# HighPowerWS2801_v2_smd.net
KiCad netlist of a schematic drawn in EAGLE
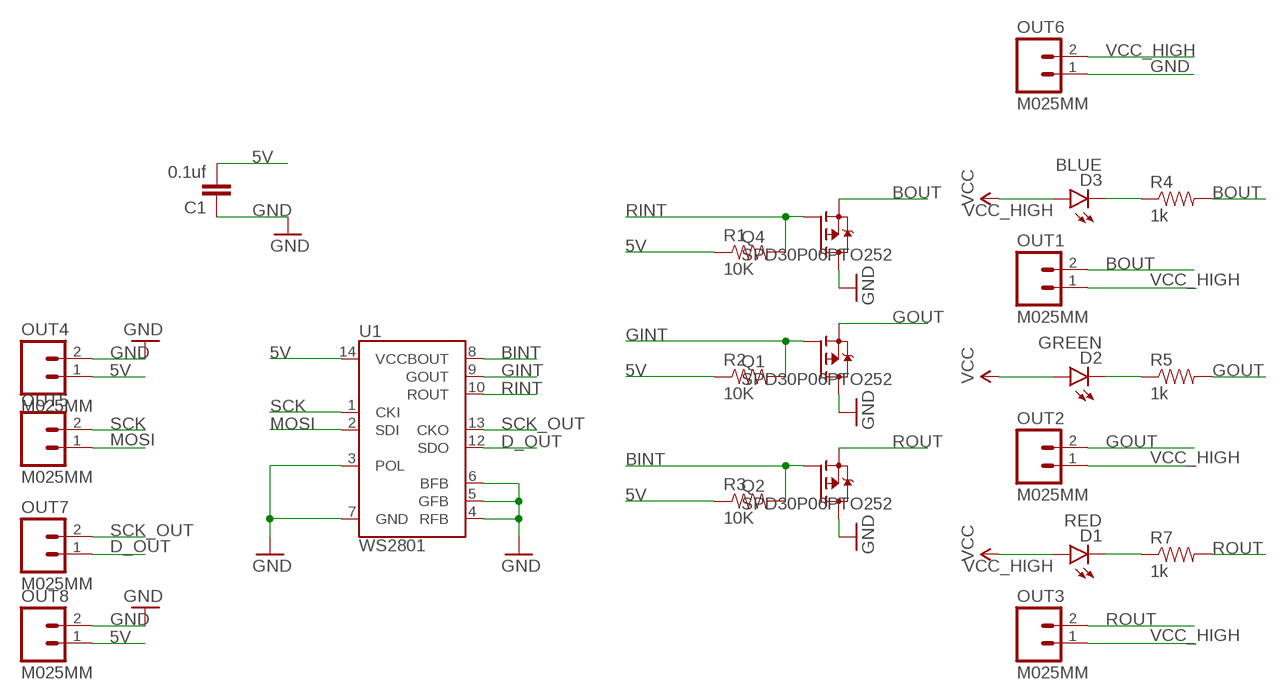
[diagram p0: schematic, sheet 1]

(export (version "E")
  (design (tool "Eeschema 10.0.6"))
  (components
    (comp (ref "C1")
      (value "0.1uf")
      (footprint "eagle-import:0603-CAP")
      (libsource (lib "eagle-import") (part "CAP0603-CAP"))
    )
    (comp (ref "D1")
      (value "RED")
      (footprint "eagle-import:LED-0603")
      (libsource (lib "eagle-import") (part "LED-RED0603"))
    )
    (comp (ref "D2")
      (value "GREEN")
      (footprint "eagle-import:LED-0603")
      (libsource (lib "eagle-import") (part "LED-GREEN0603"))
    )
    (comp (ref "D3")
      (value "BLUE")
      (footprint "eagle-import:LED-0603")
      (libsource (lib "eagle-import") (part "LED-BLUE0603"))
    )
    (comp (ref "OUT1")
      (value "M025MM")
      (footprint "eagle-import:SCREWTERMINAL-5MM-2")
      (libsource (lib "eagle-import") (part "M025MM"))
    )
    (comp (ref "OUT2")
      (value "M025MM")
      (footprint "eagle-import:SCREWTERMINAL-5MM-2")
      (libsource (lib "eagle-import") (part "M025MM"))
    )
    (comp (ref "OUT3")
      (value "M025MM")
      (footprint "eagle-import:SCREWTERMINAL-5MM-2")
      (libsource (lib "eagle-import") (part "M025MM"))
    )
    (comp (ref "OUT4")
      (value "M025MM")
      (footprint "eagle-import:SCREWTERMINAL-5MM-2")
      (libsource (lib "eagle-import") (part "M025MM"))
    )
    (comp (ref "OUT5")
      (value "M025MM")
      (footprint "eagle-import:SCREWTERMINAL-5MM-2")
      (libsource (lib "eagle-import") (part "M025MM"))
    )
    (comp (ref "OUT6")
      (value "M025MM")
      (footprint "eagle-import:SCREWTERMINAL-5MM-2")
      (libsource (lib "eagle-import") (part "M025MM"))
    )
    (comp (ref "OUT7")
      (value "M025MM")
      (footprint "eagle-import:SCREWTERMINAL-5MM-2")
      (libsource (lib "eagle-import") (part "M025MM"))
    )
    (comp (ref "OUT8")
      (value "M025MM")
      (footprint "eagle-import:SCREWTERMINAL-5MM-2")
      (libsource (lib "eagle-import") (part "M025MM"))
    )
    (comp (ref "Q1")
      (value "SPD30P06PTO252")
      (footprint "eagle-import:TO252")
      (libsource (lib "eagle-import") (part "SPD30P06PTO252"))
    )
    (comp (ref "Q2")
      (value "SPD30P06PTO252")
      (footprint "eagle-import:TO252")
      (libsource (lib "eagle-import") (part "SPD30P06PTO252"))
    )
    (comp (ref "Q4")
      (value "SPD30P06PTO252")
      (footprint "eagle-import:TO252")
      (libsource (lib "eagle-import") (part "SPD30P06PTO252"))
    )
    (comp (ref "R1")
      (value "10K")
      (footprint "eagle-import:0603-RES")
      (libsource (lib "eagle-import") (part "RESISTOR0603"))
    )
    (comp (ref "R2")
      (value "10K")
      (footprint "eagle-import:0603-RES")
      (libsource (lib "eagle-import") (part "RESISTOR0603"))
    )
    (comp (ref "R3")
      (value "10K")
      (footprint "eagle-import:0603-RES")
      (libsource (lib "eagle-import") (part "RESISTOR0603"))
    )
    (comp (ref "R4")
      (value "1k")
      (footprint "eagle-import:0603-RES")
      (libsource (lib "eagle-import") (part "RESISTOR0603"))
    )
    (comp (ref "R5")
      (value "1k")
      (footprint "eagle-import:0603-RES")
      (libsource (lib "eagle-import") (part "RESISTOR0603"))
    )
    (comp (ref "R7")
      (value "1k")
      (footprint "eagle-import:0603-RES")
      (libsource (lib "eagle-import") (part "RESISTOR0603"))
    )
    (comp (ref "U1")
      (value "WS2801")
      (footprint "eagle-import:SOP-14")
      (libsource (lib "eagle-import") (part "WS2801"))
    )
  )
  (nets
    (net (code "1") (name "/5V") (class "Default")
      (node (ref "C1") (pin "2") (pinfunction "2_2") (pintype "passive"))
      (node (ref "OUT4") (pin "1") (pinfunction "1_1") (pintype "passive"))
      (node (ref "OUT8") (pin "1") (pinfunction "1_1") (pintype "passive"))
      (node (ref "R1") (pin "1") (pinfunction "1_1") (pintype "passive"))
      (node (ref "R2") (pin "1") (pinfunction "1_1") (pintype "passive"))
      (node (ref "R3") (pin "1") (pinfunction "1_1") (pintype "passive"))
      (node (ref "U1") (pin "14") (pinfunction "VCC_14") (pintype "bidirectional"))
    )
    (net (code "2") (name "/BINT") (class "Default")
      (node (ref "Q2") (pin "1") (pinfunction "G_1") (pintype "passive"))
      (node (ref "R3") (pin "2") (pinfunction "2_2") (pintype "passive"))
      (node (ref "U1") (pin "8") (pinfunction "BOUT_8") (pintype "bidirectional"))
    )
    (net (code "3") (name "/BOUT") (class "Default")
      (node (ref "OUT1") (pin "2") (pinfunction "2_2") (pintype "passive"))
      (node (ref "Q4") (pin "2") (pinfunction "S_2") (pintype "passive"))
      (node (ref "R4") (pin "2") (pinfunction "2_2") (pintype "passive"))
    )
    (net (code "4") (name "/D_OUT") (class "Default")
      (node (ref "OUT7") (pin "1") (pinfunction "1_1") (pintype "passive"))
      (node (ref "U1") (pin "12") (pinfunction "SDO_12") (pintype "bidirectional"))
    )
    (net (code "5") (name "/GINT") (class "Default")
      (node (ref "Q1") (pin "1") (pinfunction "G_1") (pintype "passive"))
      (node (ref "R2") (pin "2") (pinfunction "2_2") (pintype "passive"))
      (node (ref "U1") (pin "9") (pinfunction "GOUT_9") (pintype "bidirectional"))
    )
    (net (code "6") (name "/GOUT") (class "Default")
      (node (ref "OUT2") (pin "2") (pinfunction "2_2") (pintype "passive"))
      (node (ref "Q1") (pin "2") (pinfunction "S_2") (pintype "passive"))
      (node (ref "R5") (pin "2") (pinfunction "2_2") (pintype "passive"))
    )
    (net (code "7") (name "/MOSI") (class "Default")
      (node (ref "OUT5") (pin "1") (pinfunction "1_1") (pintype "passive"))
      (node (ref "U1") (pin "2") (pinfunction "SDI_2") (pintype "bidirectional"))
    )
    (net (code "8") (name "/RINT") (class "Default")
      (node (ref "Q4") (pin "1") (pinfunction "G_1") (pintype "passive"))
      (node (ref "R1") (pin "2") (pinfunction "2_2") (pintype "passive"))
      (node (ref "U1") (pin "10") (pinfunction "ROUT_10") (pintype "bidirectional"))
    )
    (net (code "9") (name "/ROUT") (class "Default")
      (node (ref "OUT3") (pin "2") (pinfunction "2_2") (pintype "passive"))
      (node (ref "Q2") (pin "2") (pinfunction "S_2") (pintype "passive"))
      (node (ref "R7") (pin "2") (pinfunction "2_2") (pintype "passive"))
    )
    (net (code "10") (name "/SCK") (class "Default")
      (node (ref "OUT5") (pin "2") (pinfunction "2_2") (pintype "passive"))
      (node (ref "U1") (pin "1") (pinfunction "CKI_1") (pintype "bidirectional"))
    )
    (net (code "11") (name "/SCK_OUT") (class "Default")
      (node (ref "OUT7") (pin "2") (pinfunction "2_2") (pintype "passive"))
      (node (ref "U1") (pin "13") (pinfunction "CKO_13") (pintype "bidirectional"))
    )
    (net (code "12") (name "GND") (class "Default")
      (node (ref "C1") (pin "1") (pinfunction "1_1") (pintype "passive"))
      (node (ref "OUT4") (pin "2") (pinfunction "2_2") (pintype "passive"))
      (node (ref "OUT6") (pin "1") (pinfunction "1_1") (pintype "passive"))
      (node (ref "OUT8") (pin "2") (pinfunction "2_2") (pintype "passive"))
      (node (ref "Q1") (pin "3") (pinfunction "D_3") (pintype "passive"))
      (node (ref "Q2") (pin "3") (pinfunction "D_3") (pintype "passive"))
      (node (ref "Q4") (pin "3") (pinfunction "D_3") (pintype "passive"))
      (node (ref "U1") (pin "3") (pinfunction "POL_3") (pintype "bidirectional"))
      (node (ref "U1") (pin "4") (pinfunction "RFB_4") (pintype "bidirectional"))
      (node (ref "U1") (pin "5") (pinfunction "GFB_5") (pintype "bidirectional"))
      (node (ref "U1") (pin "6") (pinfunction "BFB_6") (pintype "bidirectional"))
      (node (ref "U1") (pin "7") (pinfunction "GND_7") (pintype "bidirectional"))
    )
    (net (code "13") (name "Net-(D1-PadC)") (class "Default")
      (node (ref "D1") (pin "C") (pinfunction "C_C") (pintype "passive"))
      (node (ref "R7") (pin "1") (pinfunction "1_1") (pintype "passive"))
    )
    (net (code "14") (name "Net-(D2-PadC)") (class "Default")
      (node (ref "D2") (pin "C") (pinfunction "C_C") (pintype "passive"))
      (node (ref "R5") (pin "1") (pinfunction "1_1") (pintype "passive"))
    )
    (net (code "15") (name "Net-(D3-PadC)") (class "Default")
      (node (ref "D3") (pin "C") (pinfunction "C_C") (pintype "passive"))
      (node (ref "R4") (pin "1") (pinfunction "1_1") (pintype "passive"))
    )
    (net (code "16") (name "VCC") (class "Default")
      (node (ref "D1") (pin "A") (pinfunction "A_A") (pintype "passive"))
      (node (ref "D2") (pin "A") (pinfunction "A_A") (pintype "passive"))
      (node (ref "D3") (pin "A") (pinfunction "A_A") (pintype "passive"))
      (node (ref "OUT1") (pin "1") (pinfunction "1_1") (pintype "passive"))
      (node (ref "OUT2") (pin "1") (pinfunction "1_1") (pintype "passive"))
      (node (ref "OUT3") (pin "1") (pinfunction "1_1") (pintype "passive"))
      (node (ref "OUT6") (pin "2") (pinfunction "2_2") (pintype "passive"))
    )
  )
)
